# ESP32_With_USBC.net
KiCad netlist of a schematic drawn in Altium Designer
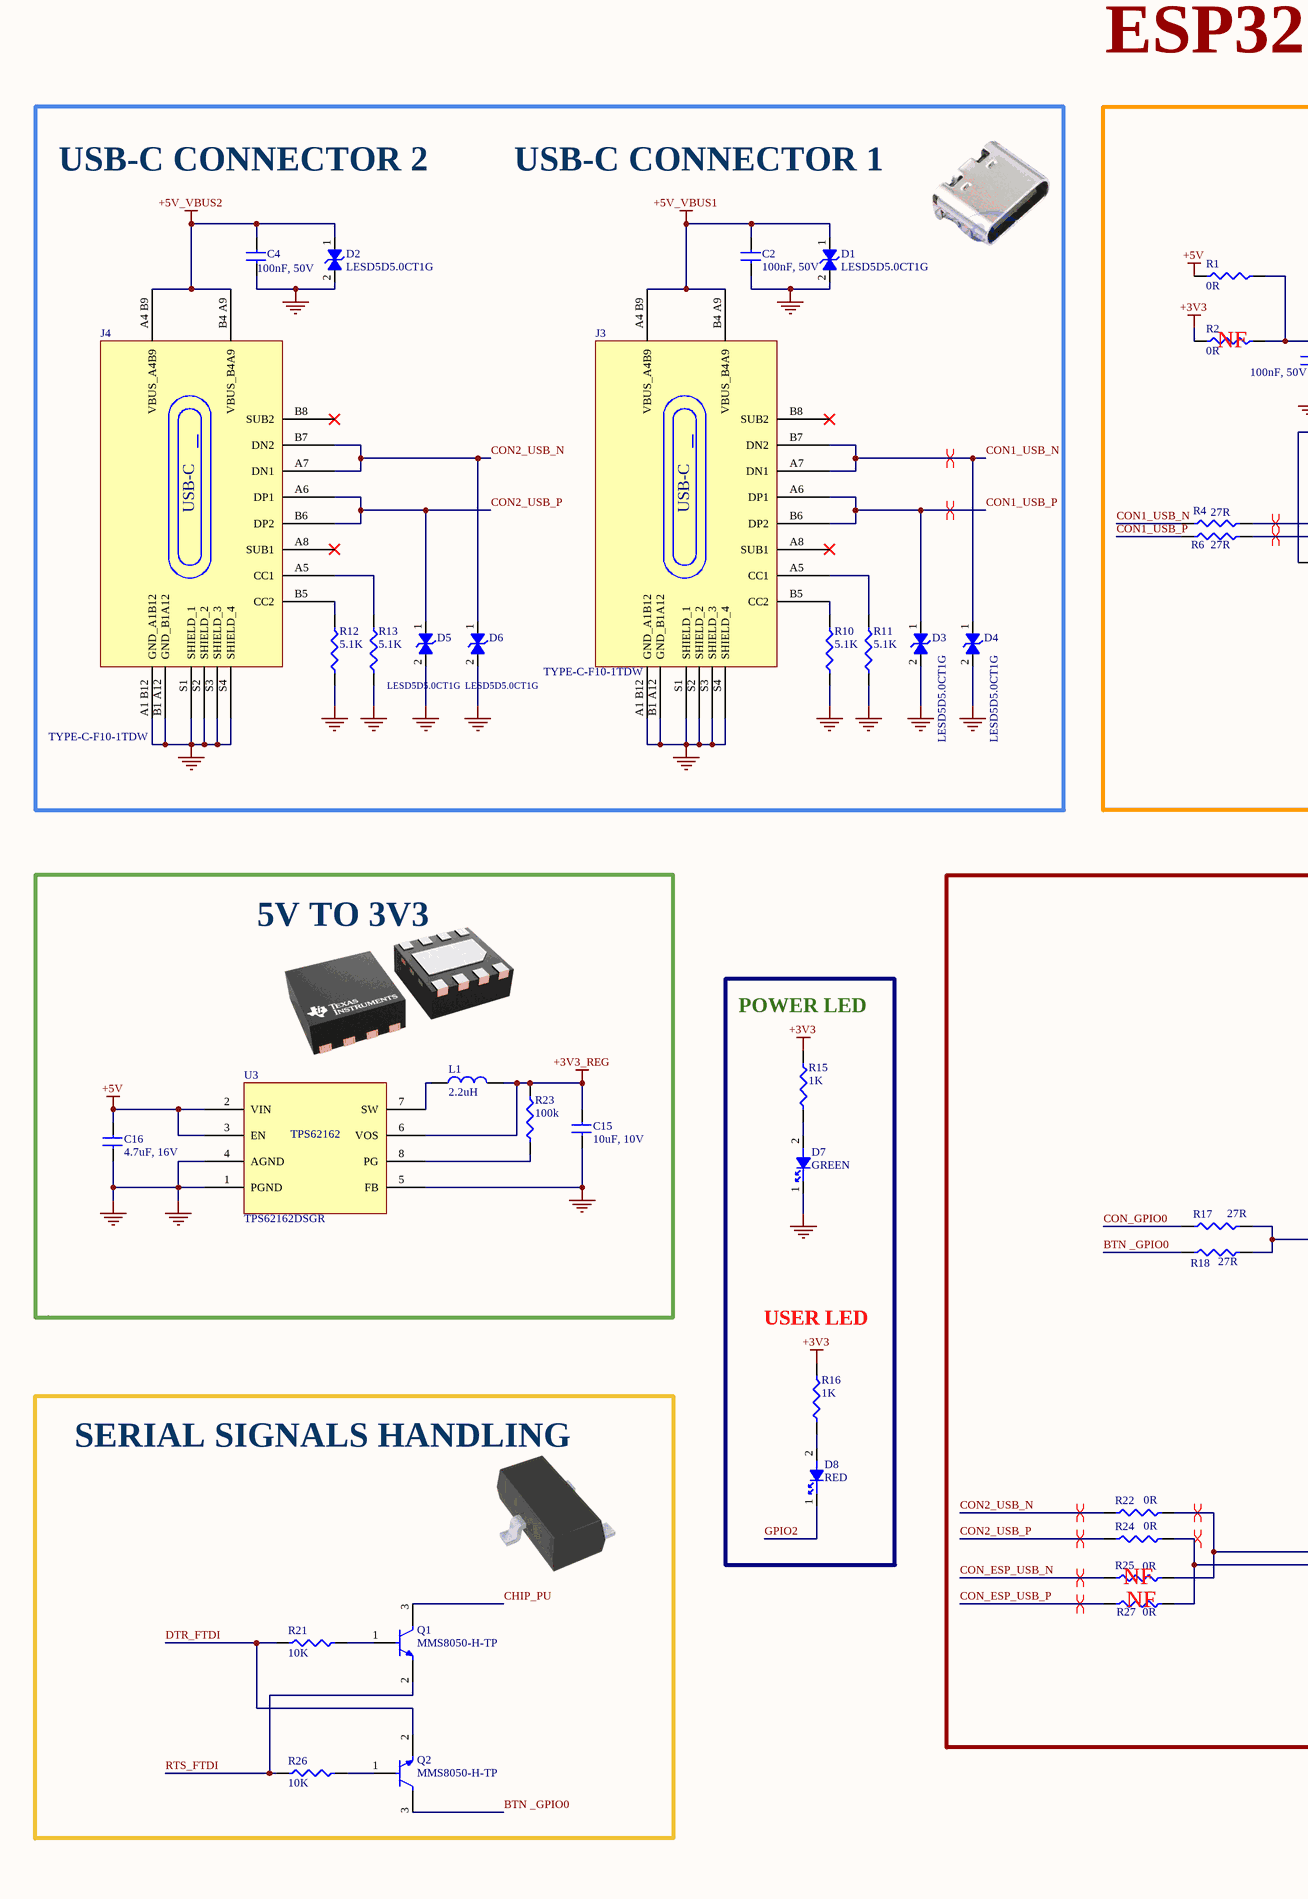
[diagram p0: ESP32 With USBC.SchDoc, left]
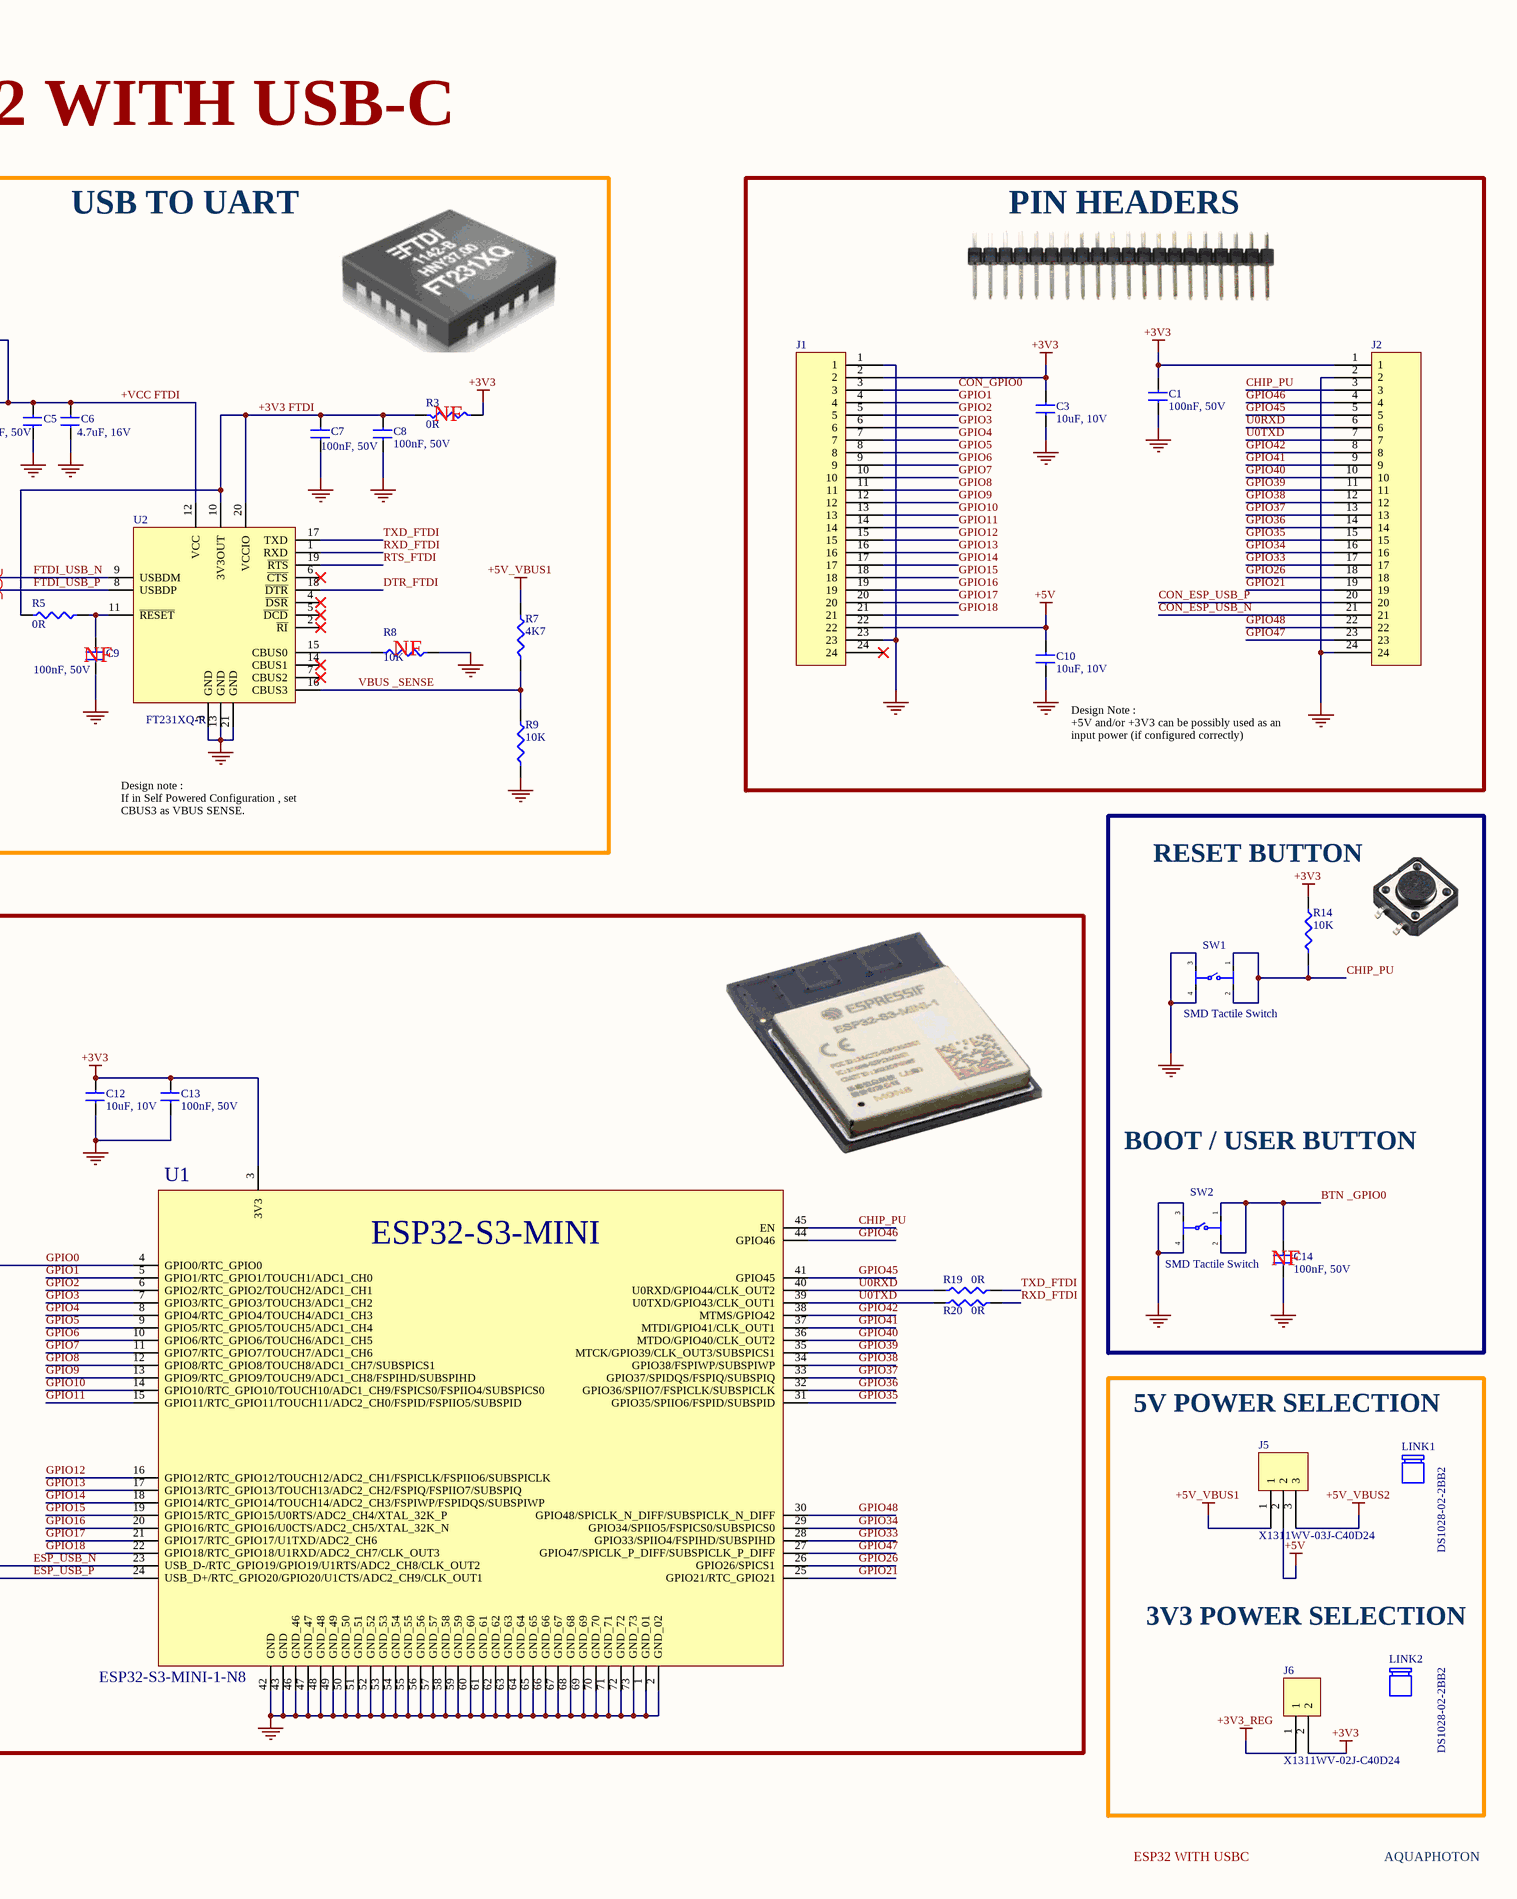
[diagram p1: ESP32 With USBC.SchDoc, right]

(export (version "E")
  (design (tool "Eeschema 10.0.6"))
  (components
    (comp (ref "C1")
      (value "100nF, 50V")
      (footprint "CAP_SMD_0402_Samsung")
      (description "CAP CER 0.1UF 50V X7R 0402")
      (fields
        (field (name "MANUFACTURER") "Samsung")
        (field (name "MANUFACTURER PART NUMBER") "CL05B104KB54PNC")
      )
      (libsource (lib "Schlib") (part "CL05B104KB54PNC"))
    )
    (comp (ref "C2")
      (value "100nF, 50V")
      (footprint "CAP_SMD_0402_Samsung")
      (description "CAP CER 0.1UF 50V X7R 0402")
      (fields
        (field (name "MANUFACTURER") "Samsung")
        (field (name "MANUFACTURER PART NUMBER") "CL05B104KB54PNC")
      )
      (libsource (lib "Schlib") (part "CL05B104KB54PNC"))
    )
    (comp (ref "C3")
      (value "10uF, 10V")
      (footprint "CAP_SMD_0402_Samsung")
      (description "CAP CER 10UF 10V X5R 0402")
      (fields
        (field (name "MANUFACTURER") "Samsung")
        (field (name "MANUFACTURER PART NUMBER") "CL05A106MP8NUB8")
      )
      (libsource (lib "Schlib") (part "CL05A106MP8NUB8"))
    )
    (comp (ref "C4")
      (value "100nF, 50V")
      (footprint "CAP_SMD_0402_Samsung")
      (description "CAP CER 0.1UF 50V X7R 0402")
      (fields
        (field (name "MANUFACTURER") "Samsung")
        (field (name "MANUFACTURER PART NUMBER") "CL05B104KB54PNC")
      )
      (libsource (lib "Schlib") (part "CL05B104KB54PNC"))
    )
    (comp (ref "C5")
      (value "100nF, 50V")
      (footprint "CAP_SMD_0402_Samsung")
      (description "CAP CER 0.1UF 50V X7R 0402")
      (fields
        (field (name "MANUFACTURER") "Samsung")
        (field (name "MANUFACTURER PART NUMBER") "CL05B104KB54PNC")
      )
      (libsource (lib "Schlib") (part "CL05B104KB54PNC"))
    )
    (comp (ref "C6")
      (value "4.7uF, 16V")
      (footprint "CAP_SMD_0402_Samsung")
      (description "4.7 µF ±20% 16V Ceramic Capacitor X5R 0402 (1005 Metric)")
      (fields
        (field (name "MANUFACTURER") "Samsung")
        (field (name "MANUFACTURER PART NUMBER") "CL05A475MO5NUNC")
      )
      (libsource (lib "Schlib") (part "CL05A475MO5NUNC"))
    )
    (comp (ref "C7")
      (value "100nF, 50V")
      (footprint "CAP_SMD_0402_Samsung")
      (description "CAP CER 0.1UF 50V X7R 0402")
      (fields
        (field (name "MANUFACTURER") "Samsung")
        (field (name "MANUFACTURER PART NUMBER") "CL05B104KB54PNC")
      )
      (libsource (lib "Schlib") (part "CL05B104KB54PNC"))
    )
    (comp (ref "C8")
      (value "100nF, 50V")
      (footprint "CAP_SMD_0402_Samsung")
      (description "CAP CER 0.1UF 50V X7R 0402")
      (fields
        (field (name "MANUFACTURER") "Samsung")
        (field (name "MANUFACTURER PART NUMBER") "CL05B104KB54PNC")
      )
      (libsource (lib "Schlib") (part "CL05B104KB54PNC"))
    )
    (comp (ref "C9")
      (value "100nF, 50V")
      (footprint "CAP_SMD_0402_Samsung")
      (description "CAP CER 0.1UF 50V X7R 0402")
      (fields
        (field (name "MANUFACTURER") "Samsung")
        (field (name "MANUFACTURER PART NUMBER") "CL05B104KB54PNC")
      )
      (libsource (lib "Schlib") (part "CL05B104KB54PNC"))
    )
    (comp (ref "C10")
      (value "10uF, 10V")
      (footprint "CAP_SMD_0402_Samsung")
      (description "CAP CER 10UF 10V X5R 0402")
      (fields
        (field (name "MANUFACTURER") "Samsung")
        (field (name "MANUFACTURER PART NUMBER") "CL05A106MP8NUB8")
      )
      (libsource (lib "Schlib") (part "CL05A106MP8NUB8"))
    )
    (comp (ref "C12")
      (value "10uF, 10V")
      (footprint "CAP_SMD_0402_Samsung")
      (description "CAP CER 10UF 10V X5R 0402")
      (fields
        (field (name "MANUFACTURER") "Samsung")
        (field (name "MANUFACTURER PART NUMBER") "CL05A106MP8NUB8")
      )
      (libsource (lib "Schlib") (part "CL05A106MP8NUB8"))
    )
    (comp (ref "C13")
      (value "100nF, 50V")
      (footprint "CAP_SMD_0402_Samsung")
      (description "CAP CER 0.1UF 50V X7R 0402")
      (fields
        (field (name "MANUFACTURER") "Samsung")
        (field (name "MANUFACTURER PART NUMBER") "CL05B104KB54PNC")
      )
      (libsource (lib "Schlib") (part "CL05B104KB54PNC"))
    )
    (comp (ref "C14")
      (value "100nF, 50V")
      (footprint "CAP_SMD_0402_Samsung")
      (description "CAP CER 0.1UF 50V X7R 0402")
      (fields
        (field (name "MANUFACTURER") "Samsung")
        (field (name "MANUFACTURER PART NUMBER") "CL05B104KB54PNC")
      )
      (libsource (lib "Schlib") (part "CL05B104KB54PNC"))
    )
    (comp (ref "C15")
      (value "10uF, 10V")
      (footprint "CAP_SMD_0402_Samsung")
      (description "CAP CER 10UF 10V X5R 0402")
      (fields
        (field (name "MANUFACTURER") "Samsung")
        (field (name "MANUFACTURER PART NUMBER") "CL05A106MP8NUB8")
      )
      (libsource (lib "Schlib") (part "CL05A106MP8NUB8"))
    )
    (comp (ref "C16")
      (value "4.7uF, 16V")
      (footprint "CAP_SMD_0402_Samsung")
      (description "4.7 µF ±20% 16V Ceramic Capacitor X5R 0402 (1005 Metric)")
      (fields
        (field (name "MANUFACTURER") "Samsung")
        (field (name "MANUFACTURER PART NUMBER") "CL05A475MO5NUNC")
      )
      (libsource (lib "Schlib") (part "CL05A475MO5NUNC"))
    )
    (comp (ref "D1")
      (value "LESD5D5.0CT1G")
      (footprint "TVS-Diode")
      (description "9.4A 18.6V 5.6V Bidirectional 5V SOD-523 ESD and Surge Protection (TVS/ESD) ROHS")
      (fields (field (name "MANUFACTURER") "LRC"))
      (libsource (lib "Schlib") (part "LESD5D5.0CT1G"))
    )
    (comp (ref "D2")
      (value "LESD5D5.0CT1G")
      (footprint "TVS-Diode")
      (description "9.4A 18.6V 5.6V Bidirectional 5V SOD-523 ESD and Surge Protection (TVS/ESD) ROHS")
      (fields (field (name "MANUFACTURER") "LRC"))
      (libsource (lib "Schlib") (part "LESD5D5.0CT1G"))
    )
    (comp (ref "D3")
      (value "LESD5D5.0CT1G")
      (footprint "TVS-Diode")
      (description "9.4A 18.6V 5.6V Bidirectional 5V SOD-523 ESD and Surge Protection (TVS/ESD) ROHS")
      (fields (field (name "MANUFACTURER") "LRC"))
      (libsource (lib "Schlib") (part "LESD5D5.0CT1G"))
    )
    (comp (ref "D4")
      (value "LESD5D5.0CT1G")
      (footprint "TVS-Diode")
      (description "9.4A 18.6V 5.6V Bidirectional 5V SOD-523 ESD and Surge Protection (TVS/ESD) ROHS")
      (fields (field (name "MANUFACTURER") "LRC"))
      (libsource (lib "Schlib") (part "LESD5D5.0CT1G"))
    )
    (comp (ref "D5")
      (value "LESD5D5.0CT1G")
      (footprint "TVS-Diode")
      (description "9.4A 18.6V 5.6V Bidirectional 5V SOD-523 ESD and Surge Protection (TVS/ESD) ROHS")
      (fields (field (name "MANUFACTURER") "LRC"))
      (libsource (lib "Schlib") (part "LESD5D5.0CT1G"))
    )
    (comp (ref "D6")
      (value "LESD5D5.0CT1G")
      (footprint "TVS-Diode")
      (description "9.4A 18.6V 5.6V Bidirectional 5V SOD-523 ESD and Surge Protection (TVS/ESD) ROHS")
      (fields (field (name "MANUFACTURER") "LRC"))
      (libsource (lib "Schlib") (part "LESD5D5.0CT1G"))
    )
    (comp (ref "D7")
      (value "GREEN")
      (footprint "LED_0402_G")
      (description "LED GREEN 0402 SMD")
      (fields
        (field (name "MANUFACTURER") "Vishay")
        (field (name "MANUFACTURER PART NUMBER") "VLMG1500-GS08")
      )
      (libsource (lib "Schlib") (part "VLMG1500-GS08"))
    )
    (comp (ref "D8")
      (value "RED")
      (footprint "LED_0402_R")
      (description "LED RED 0402 SMD")
      (fields
        (field (name "MANUFACTURER") "Vishay")
        (field (name "MANUFACTURER PART NUMBER") "VLMS1500-GS08")
      )
      (libsource (lib "Schlib") (part "VLMS1500-GS08"))
    )
    (comp (ref "J1")
      (value "X5511WV-24-C35D35-1000")
      (footprint "HDR_1X24_2.54MM")
      (fields (field (name "MANUFACTURER") "XKB Connection"))
      (libsource (lib "Schlib") (part "X6511WV-24H-C60D30"))
    )
    (comp (ref "J2")
      (value "X5511WV-24-C35D35-1000")
      (footprint "HDR_1X24_2.54MM")
      (fields (field (name "MANUFACTURER") "XKB Connection"))
      (libsource (lib "") (part "X6511WV-24H-C60D30_1"))
    )
    (comp (ref "J3")
      (value "TYPE-C-F10-1TDW")
      (footprint "USB-C")
      (description "16P Type-C SMD USB Connectors")
      (fields (field (name "MANUFACTURER") "XYECONN"))
      (libsource (lib "Schlib") (part "TYPE-C-F10-1TDW"))
    )
    (comp (ref "J4")
      (value "TYPE-C-F10-1TDW")
      (footprint "USB-C")
      (description "16P Type-C SMD USB Connectors")
      (fields (field (name "MANUFACTURER") "XYECONN"))
      (libsource (lib "Schlib") (part "TYPE-C-F10-1TDW"))
    )
    (comp (ref "J5")
      (value "X1311WV-03J-C40D24")
      (footprint "HDR_1X3_1.27mm - duplicate")
      (fields (field (name "MANUFACTURER") "XKB Connection"))
      (libsource (lib "Schlib") (part "X1311WV-03J-C40D24"))
    )
    (comp (ref "J6")
      (value "X1311WV-02J-C40D24")
      (footprint "HDR_1X2_1.27mm")
      (fields (field (name "MANUFACTURER") "XKB Connection"))
      (libsource (lib "Schlib") (part "X1311WV-02J-C40D24"))
    )
    (comp (ref "L1")
      (value "2.2uH")
      (footprint "Inductor_SMD_2.2uH")
      (description "2.2 µH Shielded Multilayer Inductor 1 A 195mOhm Max 0805 (2012 Metric)")
      (fields
        (field (name "MANUFACTURER") "TDK")
        (field (name "MANUFACTURER PART NUMBER") "MLP2012H2R2MT0S1")
      )
      (libsource (lib "Schlib") (part "MLP2012H2R2MT0S1"))
    )
    (comp (ref "LINK1")
      (value "DS1028-02-2BB2")
      (description "CONN SHUNT  1.27mm")
      (fields (field (name "MANUFACTURER") "CONNFLY Elec"))
      (libsource (lib "Schlib") (part "DS1028-02-2BB2"))
    )
    (comp (ref "LINK2")
      (value "DS1028-02-2BB2")
      (description "CONN SHUNT  1.27mm")
      (fields (field (name "MANUFACTURER") "CONNFLY Elec"))
      (libsource (lib "Schlib") (part "DS1028-02-2BB2"))
    )
    (comp (ref "Q1")
      (value "MMS8050-H-TP")
      (footprint "SOT_Transistor")
      (description "Bipolar (BJT) Transistor NPN 25 V 500 mA 150MHz 300 mW Surface Mount SOT-23")
      (fields (field (name "MANUFACTURER") "MCC"))
      (libsource (lib "Schlib") (part "MMS8050-H-TP"))
    )
    (comp (ref "Q2")
      (value "MMS8050-H-TP")
      (footprint "SOT_Transistor")
      (description "Bipolar (BJT) Transistor NPN 25 V 500 mA 150MHz 300 mW Surface Mount SOT-23")
      (fields (field (name "MANUFACTURER") "MCC"))
      (libsource (lib "Schlib") (part "MMS8050-H-TP"))
    )
    (comp (ref "R1")
      (value "0R")
      (footprint "RES_SMD_0402")
      (description "0 Ohms Jumper Chip Resistor 0402 (1005 Metric) Moisture Resistant Thick Film")
      (fields
        (field (name "MANUFACTURER") "Yageo")
        (field (name "MANUFACTURER PART NUMBER") "RC0402JR-070RL")
      )
      (libsource (lib "Schlib") (part "RC0402JR-070RL"))
    )
    (comp (ref "R2")
      (value "0R")
      (footprint "RES_SMD_0402")
      (description "0 Ohms Jumper Chip Resistor 0402 (1005 Metric) Moisture Resistant Thick Film")
      (fields
        (field (name "MANUFACTURER") "Yageo")
        (field (name "MANUFACTURER PART NUMBER") "RC0402JR-070RL")
      )
      (libsource (lib "Schlib") (part "RC0402JR-070RL"))
    )
    (comp (ref "R3")
      (value "0R")
      (footprint "RES_SMD_0402")
      (description "0 Ohms Jumper Chip Resistor 0402 (1005 Metric) Moisture Resistant Thick Film")
      (fields
        (field (name "MANUFACTURER") "Yageo")
        (field (name "MANUFACTURER PART NUMBER") "RC0402JR-070RL")
      )
      (libsource (lib "Schlib") (part "RC0402JR-070RL"))
    )
    (comp (ref "R4")
      (value "27R")
      (footprint "RES_SMD_0402")
      (description "27 Ohms ±1% 0.063W, 1/16W Chip Resistor 0402 (1005 Metric) Moisture Resistant Thick Film")
      (fields
        (field (name "MANUFACTURER") "Yageo")
        (field (name "MANUFACTURER PART NUMBER") "RC0402FR-0727RL")
      )
      (libsource (lib "Schlib") (part "RC0402FR-0727RL"))
    )
    (comp (ref "R5")
      (value "0R")
      (footprint "RES_SMD_0402")
      (description "0 Ohms Jumper Chip Resistor 0402 (1005 Metric) Moisture Resistant Thick Film")
      (fields
        (field (name "MANUFACTURER") "Yageo")
        (field (name "MANUFACTURER PART NUMBER") "RC0402JR-070RL")
      )
      (libsource (lib "Schlib") (part "RC0402JR-070RL"))
    )
    (comp (ref "R6")
      (value "27R")
      (footprint "RES_SMD_0402")
      (description "27 Ohms ±1% 0.063W, 1/16W Chip Resistor 0402 (1005 Metric) Moisture Resistant Thick Film")
      (fields
        (field (name "MANUFACTURER") "Yageo")
        (field (name "MANUFACTURER PART NUMBER") "RC0402FR-0727RL")
      )
      (libsource (lib "Schlib") (part "RC0402FR-0727RL"))
    )
    (comp (ref "R7")
      (value "4K7")
      (footprint "RES_SMD_0402")
      (description "4.7 kOhms ±1% 0.063W, 1/16W Chip Resistor 0402 (1005 Metric) Moisture Resistant Thick Film")
      (fields
        (field (name "MANUFACTURER") "Yageo")
        (field (name "MANUFACTURER PART NUMBER") "RC0402FR-074K7L")
      )
      (libsource (lib "Schlib") (part "RC0402FR-074K7L"))
    )
    (comp (ref "R8")
      (value "10K")
      (footprint "RES_SMD_0402")
      (description "62.5mW Thick Film Resistors 50V ±100ppm/℃ ±1% 10kΩ 0402 Chip Resistor - Surface Mount ROHS")
      (fields
        (field (name "MANUFACTURER") "Yageo")
        (field (name "MANUFACTURER PART NUMBER") "AC0402FR-0710KL")
      )
      (libsource (lib "Schlib") (part "AC0402FR-0710KL"))
    )
    (comp (ref "R9")
      (value "10K")
      (footprint "RES_SMD_0402")
      (description "62.5mW Thick Film Resistors 50V ±100ppm/℃ ±1% 10kΩ 0402 Chip Resistor - Surface Mount ROHS")
      (fields
        (field (name "MANUFACTURER") "Yageo")
        (field (name "MANUFACTURER PART NUMBER") "AC0402FR-0710KL")
      )
      (libsource (lib "Schlib") (part "AC0402FR-0710KL"))
    )
    (comp (ref "R10")
      (value "5.1K")
      (footprint "RES_SMD_0402")
      (fields
        (field (name "MANUFACTURER") "Yageo")
        (field (name "MANUFACTURER PART NUMBER") "AC0402FR-075K1L")
      )
      (libsource (lib "Schlib") (part "AC0402FR-075K1L"))
    )
    (comp (ref "R11")
      (value "5.1K")
      (footprint "RES_SMD_0402")
      (fields
        (field (name "MANUFACTURER") "Yageo")
        (field (name "MANUFACTURER PART NUMBER") "AC0402FR-075K1L")
      )
      (libsource (lib "Schlib") (part "AC0402FR-075K1L"))
    )
    (comp (ref "R12")
      (value "5.1K")
      (footprint "RES_SMD_0402")
      (fields
        (field (name "MANUFACTURER") "Yageo")
        (field (name "MANUFACTURER PART NUMBER") "AC0402FR-075K1L")
      )
      (libsource (lib "Schlib") (part "AC0402FR-075K1L"))
    )
    (comp (ref "R13")
      (value "5.1K")
      (footprint "RES_SMD_0402")
      (fields
        (field (name "MANUFACTURER") "Yageo")
        (field (name "MANUFACTURER PART NUMBER") "AC0402FR-075K1L")
      )
      (libsource (lib "Schlib") (part "AC0402FR-075K1L"))
    )
    (comp (ref "R14")
      (value "10K")
      (footprint "RES_SMD_0402")
      (description "62.5mW Thick Film Resistors 50V ±100ppm/℃ ±1% 10kΩ 0402 Chip Resistor - Surface Mount ROHS")
      (fields
        (field (name "MANUFACTURER") "Yageo")
        (field (name "MANUFACTURER PART NUMBER") "AC0402FR-0710KL")
      )
      (libsource (lib "Schlib") (part "AC0402FR-0710KL"))
    )
    (comp (ref "R15")
      (value "1K")
      (footprint "RES_SMD_0402")
      (description "RES 1K OHM 1% 1/16W 0402")
      (fields
        (field (name "MANUFACTURER") "Yageo")
        (field (name "MANUFACTURER PART NUMBER") "RC0402FR-071KL")
      )
      (libsource (lib "Schlib") (part "RC0402FR-071KL"))
    )
    (comp (ref "R16")
      (value "1K")
      (footprint "RES_SMD_0402")
      (description "RES 1K OHM 1% 1/16W 0402")
      (fields
        (field (name "MANUFACTURER") "Yageo")
        (field (name "MANUFACTURER PART NUMBER") "RC0402FR-071KL")
      )
      (libsource (lib "Schlib") (part "RC0402FR-071KL"))
    )
    (comp (ref "R17")
      (value "27R")
      (footprint "RES_SMD_0402")
      (description "27 Ohms ±1% 0.063W, 1/16W Chip Resistor 0402 (1005 Metric) Moisture Resistant Thick Film")
      (fields
        (field (name "MANUFACTURER") "Yageo")
        (field (name "MANUFACTURER PART NUMBER") "RC0402FR-0727RL")
      )
      (libsource (lib "Schlib") (part "RC0402FR-0727RL"))
    )
    (comp (ref "R18")
      (value "27R")
      (footprint "RES_SMD_0402")
      (description "27 Ohms ±1% 0.063W, 1/16W Chip Resistor 0402 (1005 Metric) Moisture Resistant Thick Film")
      (fields
        (field (name "MANUFACTURER") "Yageo")
        (field (name "MANUFACTURER PART NUMBER") "RC0402FR-0727RL")
      )
      (libsource (lib "Schlib") (part "RC0402FR-0727RL"))
    )
    (comp (ref "R19")
      (value "0R")
      (footprint "RES_SMD_0402")
      (description "0 Ohms Jumper Chip Resistor 0402 (1005 Metric) Moisture Resistant Thick Film")
      (fields
        (field (name "MANUFACTURER") "Yageo")
        (field (name "MANUFACTURER PART NUMBER") "RC0402JR-070RL")
      )
      (libsource (lib "Schlib") (part "RC0402JR-070RL"))
    )
    (comp (ref "R20")
      (value "0R")
      (footprint "RES_SMD_0402")
      (description "0 Ohms Jumper Chip Resistor 0402 (1005 Metric) Moisture Resistant Thick Film")
      (fields
        (field (name "MANUFACTURER") "Yageo")
        (field (name "MANUFACTURER PART NUMBER") "RC0402JR-070RL")
      )
      (libsource (lib "Schlib") (part "RC0402JR-070RL"))
    )
    (comp (ref "R21")
      (value "10K")
      (footprint "RES_SMD_0402")
      (description "62.5mW Thick Film Resistors 50V ±100ppm/℃ ±1% 10kΩ 0402 Chip Resistor - Surface Mount ROHS")
      (fields
        (field (name "MANUFACTURER") "Yageo")
        (field (name "MANUFACTURER PART NUMBER") "AC0402FR-0710KL")
      )
      (libsource (lib "Schlib") (part "AC0402FR-0710KL"))
    )
    (comp (ref "R22")
      (value "0R")
      (footprint "RES_SMD_0402")
      (description "0 Ohms Jumper Chip Resistor 0402 (1005 Metric) Moisture Resistant Thick Film")
      (fields
        (field (name "MANUFACTURER") "Yageo")
        (field (name "MANUFACTURER PART NUMBER") "RC0402JR-070RL")
      )
      (libsource (lib "Schlib") (part "RC0402JR-070RL"))
    )
    (comp (ref "R23")
      (value "100k")
      (footprint "RES_SMD_0402")
      (description "RES SMD 100K OHM 1% 1/16W 0402")
      (fields
        (field (name "MANUFACTURER") "Yageo")
        (field (name "MANUFACTURER PART NUMBER") "AC0402FR-07100KL")
      )
      (libsource (lib "Schlib") (part "AC0402FR-07100KL"))
    )
    (comp (ref "R24")
      (value "0R")
      (footprint "RES_SMD_0402")
      (description "0 Ohms Jumper Chip Resistor 0402 (1005 Metric) Moisture Resistant Thick Film")
      (fields
        (field (name "MANUFACTURER") "Yageo")
        (field (name "MANUFACTURER PART NUMBER") "RC0402JR-070RL")
      )
      (libsource (lib "Schlib") (part "RC0402JR-070RL"))
    )
    (comp (ref "R25")
      (value "0R")
      (footprint "RES_SMD_0402")
      (description "0 Ohms Jumper Chip Resistor 0402 (1005 Metric) Moisture Resistant Thick Film")
      (fields
        (field (name "MANUFACTURER") "Yageo")
        (field (name "MANUFACTURER PART NUMBER") "RC0402JR-070RL")
      )
      (libsource (lib "Schlib") (part "RC0402JR-070RL"))
    )
    (comp (ref "R26")
      (value "10K")
      (footprint "RES_SMD_0402")
      (description "62.5mW Thick Film Resistors 50V ±100ppm/℃ ±1% 10kΩ 0402 Chip Resistor - Surface Mount ROHS")
      (fields
        (field (name "MANUFACTURER") "Yageo")
        (field (name "MANUFACTURER PART NUMBER") "AC0402FR-0710KL")
      )
      (libsource (lib "Schlib") (part "AC0402FR-0710KL"))
    )
    (comp (ref "R27")
      (value "0R")
      (footprint "RES_SMD_0402")
      (description "0 Ohms Jumper Chip Resistor 0402 (1005 Metric) Moisture Resistant Thick Film")
      (fields
        (field (name "MANUFACTURER") "Yageo")
        (field (name "MANUFACTURER PART NUMBER") "RC0402JR-070RL")
      )
      (libsource (lib "Schlib") (part "RC0402JR-070RL"))
    )
    (comp (ref "SW1")
      (value "SMD Tactile Switch")
      (footprint "Tactile Switch_SMD")
      (description "SMD Tactile Switches ROHS")
      (fields
        (field (name "MANUFACTURER") "G-Switch")
        (field (name "MANUFACTURER PART NUMBER") "GT-TC089A-H043-L1")
      )
      (libsource (lib "Schlib") (part "GT-TC089A-H043-L1"))
    )
    (comp (ref "SW2")
      (value "SMD Tactile Switch")
      (footprint "Tactile Switch_SMD")
      (description "SMD Tactile Switches ROHS")
      (fields
        (field (name "MANUFACTURER") "G-Switch")
        (field (name "MANUFACTURER PART NUMBER") "GT-TC089A-H043-L1")
      )
      (libsource (lib "Schlib") (part "GT-TC089A-H043-L1"))
    )
    (comp (ref "U1")
      (value "ESP32-S3-MINI-1-N8")
      (footprint "ESP32-S3-MINI-1-N8")
      (description "SMD module, ESP32-S3FN8, 8 MB SPI flash, PCB antenna")
      (fields (field (name "MANUFACTURER") "Espressif Systems"))
      (libsource (lib "Schlib") (part "ESP32-S3-MINI-1-N8"))
    )
    (comp (ref "U2")
      (value "FT231XQ-R")
      (footprint "USB TO UART _FTDI")
      (description "IC USB SERIAL FULL UART 20QFN")
      (fields (field (name "MANUFACTURER") "FTDI"))
      (libsource (lib "Schlib") (part "FT231XQ-R"))
    )
    (comp (ref "U3")
      (value "TPS62162DSGR")
      (footprint "BUCK_TPS62162DSGR")
      (description "Buck Switching Regulator IC Positive Fixed 3.3V 1 Output 1A 8-WFDFN Exposed Pad")
      (fields (field (name "MANUFACTURER") "Texas Instruments"))
      (libsource (lib "Schlib") (part "TPS62162DSGR"))
    )
  )
  (nets
    (net (code "1") (name "+3V3") (class "Default")
      (node (ref "C1") (pin "2") (pinfunction "2_2") (pintype "passive"))
      (node (ref "C12") (pin "2") (pinfunction "2_2") (pintype "passive"))
      (node (ref "C13") (pin "2") (pinfunction "2_2") (pintype "passive"))
      (node (ref "C3") (pin "2") (pinfunction "2_2") (pintype "passive"))
      (node (ref "J1") (pin "2") (pinfunction "2_2") (pintype "passive"))
      (node (ref "J2") (pin "1") (pinfunction "1_1") (pintype "passive"))
      (node (ref "J6") (pin "2") (pinfunction "2_2") (pintype "passive"))
      (node (ref "R14") (pin "2") (pinfunction "2_2") (pintype "passive"))
      (node (ref "R15") (pin "2") (pinfunction "2_2") (pintype "passive"))
      (node (ref "R16") (pin "2") (pinfunction "2_2") (pintype "passive"))
      (node (ref "R2") (pin "1") (pinfunction "1_1") (pintype "passive"))
      (node (ref "R3") (pin "1") (pinfunction "1_1") (pintype "passive"))
      (node (ref "U1") (pin "3") (pinfunction "3V3_3") (pintype "passive"))
    )
    (net (code "2") (name "+3V3_REG") (class "Default")
      (node (ref "C15") (pin "2") (pinfunction "2_2") (pintype "passive"))
      (node (ref "J6") (pin "1") (pinfunction "1_1") (pintype "passive"))
      (node (ref "L1") (pin "2") (pinfunction "2_2") (pintype "passive"))
      (node (ref "R23") (pin "2") (pinfunction "2_2") (pintype "passive"))
      (node (ref "U3") (pin "6") (pinfunction "VOS_6") (pintype "passive"))
    )
    (net (code "3") (name "+5V") (class "Default")
      (node (ref "C10") (pin "2") (pinfunction "2_2") (pintype "passive"))
      (node (ref "C16") (pin "2") (pinfunction "2_2") (pintype "passive"))
      (node (ref "J1") (pin "22") (pinfunction "22_22") (pintype "passive"))
      (node (ref "J5") (pin "2") (pinfunction "2_2") (pintype "passive"))
      (node (ref "R1") (pin "1") (pinfunction "1_1") (pintype "passive"))
      (node (ref "U3") (pin "2") (pinfunction "VIN_2") (pintype "passive"))
      (node (ref "U3") (pin "3") (pinfunction "EN_3") (pintype "passive"))
    )
    (net (code "4") (name "+5V_VBUS1") (class "Default")
      (node (ref "C2") (pin "2") (pinfunction "2_2") (pintype "passive"))
      (node (ref "D1") (pin "1") (pinfunction "1_1") (pintype "passive"))
      (node (ref "J3") (pin "A4_B9") (pinfunction "VBUS_A4B9_A4_B9") (pintype "passive"))
      (node (ref "J3") (pin "B4_A9") (pinfunction "VBUS_B4A9_B4_A9") (pintype "passive"))
      (node (ref "J5") (pin "1") (pinfunction "1_1") (pintype "passive"))
      (node (ref "R7") (pin "2") (pinfunction "2_2") (pintype "passive"))
    )
    (net (code "5") (name "+5V_VBUS2") (class "Default")
      (node (ref "C4") (pin "2") (pinfunction "2_2") (pintype "passive"))
      (node (ref "D2") (pin "1") (pinfunction "1_1") (pintype "passive"))
      (node (ref "J4") (pin "A4_B9") (pinfunction "VBUS_A4B9_A4_B9") (pintype "passive"))
      (node (ref "J4") (pin "B4_A9") (pinfunction "VBUS_B4A9_B4_A9") (pintype "passive"))
      (node (ref "J5") (pin "3") (pinfunction "3_3") (pintype "passive"))
    )
    (net (code "6") (name "/+3V3 FTDI") (class "Default")
      (node (ref "C7") (pin "2") (pinfunction "2_2") (pintype "passive"))
      (node (ref "C8") (pin "2") (pinfunction "2_2") (pintype "passive"))
      (node (ref "R3") (pin "2") (pinfunction "2_2") (pintype "passive"))
      (node (ref "R5") (pin "1") (pinfunction "1_1") (pintype "passive"))
      (node (ref "U2") (pin "10") (pinfunction "3V3OUT_10") (pintype "passive"))
      (node (ref "U2") (pin "20") (pinfunction "VCCIO_20") (pintype "passive"))
    )
    (net (code "7") (name "/+VCC FTDI") (class "Default")
      (node (ref "C5") (pin "2") (pinfunction "2_2") (pintype "passive"))
      (node (ref "C6") (pin "2") (pinfunction "2_2") (pintype "passive"))
      (node (ref "R1") (pin "2") (pinfunction "2_2") (pintype "passive"))
      (node (ref "R2") (pin "2") (pinfunction "2_2") (pintype "passive"))
      (node (ref "U2") (pin "12") (pinfunction "VCC_12") (pintype "passive"))
    )
    (net (code "8") (name "/BTN _GPIO0") (class "Default")
      (node (ref "C14") (pin "2") (pinfunction "2_2") (pintype "passive"))
      (node (ref "Q2") (pin "3") (pinfunction "C_3") (pintype "passive"))
      (node (ref "R18") (pin "1") (pinfunction "1_1") (pintype "passive"))
      (node (ref "SW2") (pin "1") (pinfunction "1_1") (pintype "passive"))
      (node (ref "SW2") (pin "2") (pinfunction "2_2") (pintype "passive"))
    )
    (net (code "9") (name "/CHIP_PU") (class "Default")
      (node (ref "J2") (pin "3") (pinfunction "3_3") (pintype "passive"))
      (node (ref "Q1") (pin "3") (pinfunction "C_3") (pintype "passive"))
      (node (ref "R14") (pin "1") (pinfunction "1_1") (pintype "passive"))
      (node (ref "SW1") (pin "1") (pinfunction "1_1") (pintype "passive"))
      (node (ref "SW1") (pin "2") (pinfunction "2_2") (pintype "passive"))
      (node (ref "U1") (pin "45") (pinfunction "EN_45") (pintype "passive"))
    )
    (net (code "10") (name "/CON1_USB_N") (class "Default")
      (node (ref "D4") (pin "1") (pinfunction "1_1") (pintype "passive"))
      (node (ref "J3") (pin "A7") (pinfunction "DN1_A7") (pintype "passive"))
      (node (ref "J3") (pin "B7") (pinfunction "DN2_B7") (pintype "passive"))
      (node (ref "R4") (pin "1") (pinfunction "1_1") (pintype "passive"))
    )
    (net (code "11") (name "/CON1_USB_P") (class "Default")
      (node (ref "D3") (pin "1") (pinfunction "1_1") (pintype "passive"))
      (node (ref "J3") (pin "A6") (pinfunction "DP1_A6") (pintype "passive"))
      (node (ref "J3") (pin "B6") (pinfunction "DP2_B6") (pintype "passive"))
      (node (ref "R6") (pin "1") (pinfunction "1_1") (pintype "passive"))
    )
    (net (code "12") (name "/CON2_USB_N") (class "Default")
      (node (ref "D6") (pin "1") (pinfunction "1_1") (pintype "passive"))
      (node (ref "J4") (pin "A7") (pinfunction "DN1_A7") (pintype "passive"))
      (node (ref "J4") (pin "B7") (pinfunction "DN2_B7") (pintype "passive"))
      (node (ref "R22") (pin "1") (pinfunction "1_1") (pintype "passive"))
    )
    (net (code "13") (name "/CON2_USB_P") (class "Default")
      (node (ref "D5") (pin "1") (pinfunction "1_1") (pintype "passive"))
      (node (ref "J4") (pin "A6") (pinfunction "DP1_A6") (pintype "passive"))
      (node (ref "J4") (pin "B6") (pinfunction "DP2_B6") (pintype "passive"))
      (node (ref "R24") (pin "1") (pinfunction "1_1") (pintype "passive"))
    )
    (net (code "14") (name "/CON_ESP_USB_N") (class "Default")
      (node (ref "J2") (pin "21") (pinfunction "21_21") (pintype "passive"))
      (node (ref "R25") (pin "1") (pinfunction "1_1") (pintype "passive"))
    )
    (net (code "15") (name "/CON_ESP_USB_P") (class "Default")
      (node (ref "J2") (pin "20") (pinfunction "20_20") (pintype "passive"))
      (node (ref "R27") (pin "1") (pinfunction "1_1") (pintype "passive"))
    )
    (net (code "16") (name "/CON_GPIO0") (class "Default")
      (node (ref "J1") (pin "3") (pinfunction "3_3") (pintype "passive"))
      (node (ref "R17") (pin "1") (pinfunction "1_1") (pintype "passive"))
    )
    (net (code "17") (name "/DTR_FTDI") (class "Default")
      (node (ref "Q2") (pin "2") (pinfunction "E_2") (pintype "passive"))
      (node (ref "R21") (pin "2") (pinfunction "2_2") (pintype "passive"))
      (node (ref "U2") (pin "18") (pinfunction "~{DTR}_18") (pintype "passive"))
    )
    (net (code "18") (name "/ESP_USB_N") (class "Default")
      (node (ref "R22") (pin "2") (pinfunction "2_2") (pintype "passive"))
      (node (ref "R25") (pin "2") (pinfunction "2_2") (pintype "passive"))
      (node (ref "U1") (pin "23") (pinfunction "USB_D-/RTC_GPIO19/GPIO19/U1RTS/ADC2_CH8/CLK_OUT2_23") (pintype "passive"))
    )
    (net (code "19") (name "/ESP_USB_P") (class "Default")
      (node (ref "R24") (pin "2") (pinfunction "2_2") (pintype "passive"))
      (node (ref "R27") (pin "2") (pinfunction "2_2") (pintype "passive"))
      (node (ref "U1") (pin "24") (pinfunction "USB_D+/RTC_GPIO20/GPIO20/U1CTS/ADC2_CH9/CLK_OUT1_24") (pintype "passive"))
    )
    (net (code "20") (name "/FTDI_USB_N") (class "Default")
      (node (ref "R4") (pin "2") (pinfunction "2_2") (pintype "passive"))
      (node (ref "U2") (pin "9") (pinfunction "USBDM_9") (pintype "passive"))
    )
    (net (code "21") (name "/FTDI_USB_P") (class "Default")
      (node (ref "R6") (pin "2") (pinfunction "2_2") (pintype "passive"))
      (node (ref "U2") (pin "8") (pinfunction "USBDP_8") (pintype "passive"))
    )
    (net (code "22") (name "/GPIO0") (class "Default")
      (node (ref "R17") (pin "2") (pinfunction "2_2") (pintype "passive"))
      (node (ref "R18") (pin "2") (pinfunction "2_2") (pintype "passive"))
      (node (ref "U1") (pin "4") (pinfunction "GPIO0/RTC_GPIO0_4") (pintype "passive"))
    )
    (net (code "23") (name "/GPIO1") (class "Default")
      (node (ref "J1") (pin "4") (pinfunction "4_4") (pintype "passive"))
      (node (ref "U1") (pin "5") (pinfunction "GPIO1/RTC_GPIO1/TOUCH1/ADC1_CH0_5") (pintype "passive"))
    )
    (net (code "24") (name "/GPIO2") (class "Default")
      (node (ref "D8") (pin "1") (pinfunction "1_1") (pintype "passive"))
      (node (ref "J1") (pin "5") (pinfunction "5_5") (pintype "passive"))
      (node (ref "U1") (pin "6") (pinfunction "GPIO2/RTC_GPIO2/TOUCH2/ADC1_CH1_6") (pintype "passive"))
    )
    (net (code "25") (name "/GPIO3") (class "Default")
      (node (ref "J1") (pin "6") (pinfunction "6_6") (pintype "passive"))
      (node (ref "U1") (pin "7") (pinfunction "GPIO3/RTC_GPIO3/TOUCH3/ADC1_CH2_7") (pintype "passive"))
    )
    (net (code "26") (name "/GPIO4") (class "Default")
      (node (ref "J1") (pin "7") (pinfunction "7_7") (pintype "passive"))
      (node (ref "U1") (pin "8") (pinfunction "GPIO4/RTC_GPIO4/TOUCH4/ADC1_CH3_8") (pintype "passive"))
    )
    (net (code "27") (name "/GPIO5") (class "Default")
      (node (ref "J1") (pin "8") (pinfunction "8_8") (pintype "passive"))
      (node (ref "U1") (pin "9") (pinfunction "GPIO5/RTC_GPIO5/TOUCH5/ADC1_CH4_9") (pintype "passive"))
    )
    (net (code "28") (name "/GPIO6") (class "Default")
      (node (ref "J1") (pin "9") (pinfunction "9_9") (pintype "passive"))
      (node (ref "U1") (pin "10") (pinfunction "GPIO6/RTC_GPIO6/TOUCH6/ADC1_CH5_10") (pintype "passive"))
    )
    (net (code "29") (name "/GPIO7") (class "Default")
      (node (ref "J1") (pin "10") (pinfunction "10_10") (pintype "passive"))
      (node (ref "U1") (pin "11") (pinfunction "GPIO7/RTC_GPIO7/TOUCH7/ADC1_CH6_11") (pintype "passive"))
    )
    (net (code "30") (name "/GPIO8") (class "Default")
      (node (ref "J1") (pin "11") (pinfunction "11_11") (pintype "passive"))
      (node (ref "U1") (pin "12") (pinfunction "GPIO8/RTC_GPIO8/TOUCH8/ADC1_CH7/SUBSPICS1_12") (pintype "passive"))
    )
    (net (code "31") (name "/GPIO9") (class "Default")
      (node (ref "J1") (pin "12") (pinfunction "12_12") (pintype "passive"))
      (node (ref "U1") (pin "13") (pinfunction "GPIO9/RTC_GPIO9/TOUCH9/ADC1_CH8/FSPIHD/SUBSPIHD_13") (pintype "passive"))
    )
    (net (code "32") (name "/GPIO10") (class "Default")
      (node (ref "J1") (pin "13") (pinfunction "13_13") (pintype "passive"))
      (node (ref "U1") (pin "14") (pinfunction "GPIO10/RTC_GPIO10/TOUCH10/ADC1_CH9/FSPICS0/FSPIIO4/SUBSPICS0_14") (pintype "passive"))
    )
    (net (code "33") (name "/GPIO11") (class "Default")
      (node (ref "J1") (pin "14") (pinfunction "14_14") (pintype "passive"))
      (node (ref "U1") (pin "15") (pinfunction "GPIO11/RTC_GPIO11/TOUCH11/ADC2_CH0/FSPID/FSPIIO5/SUBSPID_15") (pintype "passive"))
    )
    (net (code "34") (name "/GPIO12") (class "Default")
      (node (ref "J1") (pin "15") (pinfunction "15_15") (pintype "passive"))
      (node (ref "U1") (pin "16") (pinfunction "GPIO12/RTC_GPIO12/TOUCH12/ADC2_CH1/FSPICLK/FSPIIO6/SUBSPICLK_16") (pintype "passive"))
    )
    (net (code "35") (name "/GPIO13") (class "Default")
      (node (ref "J1") (pin "16") (pinfunction "16_16") (pintype "passive"))
      (node (ref "U1") (pin "17") (pinfunction "GPIO13/RTC_GPIO13/TOUCH13/ADC2_CH2/FSPIQ/FSPIIO7/SUBSPIQ_17") (pintype "passive"))
    )
    (net (code "36") (name "/GPIO14") (class "Default")
      (node (ref "J1") (pin "17") (pinfunction "17_17") (pintype "passive"))
      (node (ref "U1") (pin "18") (pinfunction "GPIO14/RTC_GPIO14/TOUCH14/ADC2_CH3/FSPIWP/FSPIDQS/SUBSPIWP_18") (pintype "passive"))
    )
    (net (code "37") (name "/GPIO15") (class "Default")
      (node (ref "J1") (pin "18") (pinfunction "18_18") (pintype "passive"))
      (node (ref "U1") (pin "19") (pinfunction "GPIO15/RTC_GPIO15/U0RTS/ADC2_CH4/XTAL_32K_P_19") (pintype "passive"))
    )
    (net (code "38") (name "/GPIO16") (class "Default")
      (node (ref "J1") (pin "19") (pinfunction "19_19") (pintype "passive"))
      (node (ref "U1") (pin "20") (pinfunction "GPIO16/RTC_GPIO16/U0CTS/ADC2_CH5/XTAL_32K_N_20") (pintype "passive"))
    )
    (net (code "39") (name "/GPIO17") (class "Default")
      (node (ref "J1") (pin "20") (pinfunction "20_20") (pintype "passive"))
      (node (ref "U1") (pin "21") (pinfunction "GPIO17/RTC_GPIO17/U1TXD/ADC2_CH6_21") (pintype "passive"))
    )
    (net (code "40") (name "/GPIO18") (class "Default")
      (node (ref "J1") (pin "21") (pinfunction "21_21") (pintype "passive"))
      (node (ref "U1") (pin "22") (pinfunction "GPIO18/RTC_GPIO18/U1RXD/ADC2_CH7/CLK_OUT3_22") (pintype "passive"))
    )
    (net (code "41") (name "/GPIO21") (class "Default")
      (node (ref "J2") (pin "19") (pinfunction "19_19") (pintype "passive"))
      (node (ref "U1") (pin "25") (pinfunction "GPIO21/RTC_GPIO21_25") (pintype "passive"))
    )
    (net (code "42") (name "/GPIO26") (class "Default")
      (node (ref "J2") (pin "18") (pinfunction "18_18") (pintype "passive"))
      (node (ref "U1") (pin "26") (pinfunction "GPIO26/SPICS1_26") (pintype "passive"))
    )
    (net (code "43") (name "/GPIO33") (class "Default")
      (node (ref "J2") (pin "17") (pinfunction "17_17") (pintype "passive"))
      (node (ref "U1") (pin "28") (pinfunction "GPIO33/SPIIO4/FSPIHD/SUBSPIHD_28") (pintype "passive"))
    )
    (net (code "44") (name "/GPIO34") (class "Default")
      (node (ref "J2") (pin "16") (pinfunction "16_16") (pintype "passive"))
      (node (ref "U1") (pin "29") (pinfunction "GPIO34/SPIIO5/FSPICS0/SUBSPICS0_29") (pintype "passive"))
    )
    (net (code "45") (name "/GPIO35") (class "Default")
      (node (ref "J2") (pin "15") (pinfunction "15_15") (pintype "passive"))
      (node (ref "U1") (pin "31") (pinfunction "GPIO35/SPIIO6/FSPID/SUBSPID_31") (pintype "passive"))
    )
    (net (code "46") (name "/GPIO36") (class "Default")
      (node (ref "J2") (pin "14") (pinfunction "14_14") (pintype "passive"))
      (node (ref "U1") (pin "32") (pinfunction "GPIO36/SPIIO7/FSPICLK/SUBSPICLK_32") (pintype "passive"))
    )
    (net (code "47") (name "/GPIO37") (class "Default")
      (node (ref "J2") (pin "13") (pinfunction "13_13") (pintype "passive"))
      (node (ref "U1") (pin "33") (pinfunction "GPIO37/SPIDQS/FSPIQ/SUBSPIQ_33") (pintype "passive"))
    )
    (net (code "48") (name "/GPIO38") (class "Default")
      (node (ref "J2") (pin "12") (pinfunction "12_12") (pintype "passive"))
      (node (ref "U1") (pin "34") (pinfunction "GPIO38/FSPIWP/SUBSPIWP_34") (pintype "passive"))
    )
    (net (code "49") (name "/GPIO39") (class "Default")
      (node (ref "J2") (pin "11") (pinfunction "11_11") (pintype "passive"))
      (node (ref "U1") (pin "35") (pinfunction "MTCK/GPIO39/CLK_OUT3/SUBSPICS1_35") (pintype "passive"))
    )
    (net (code "50") (name "/GPIO40") (class "Default")
      (node (ref "J2") (pin "10") (pinfunction "10_10") (pintype "passive"))
      (node (ref "U1") (pin "36") (pinfunction "MTDO/GPIO40/CLK_OUT2_36") (pintype "passive"))
    )
    (net (code "51") (name "/GPIO41") (class "Default")
      (node (ref "J2") (pin "9") (pinfunction "9_9") (pintype "passive"))
      (node (ref "U1") (pin "37") (pinfunction "MTDI/GPIO41/CLK_OUT1_37") (pintype "passive"))
    )
    (net (code "52") (name "/GPIO42") (class "Default")
      (node (ref "J2") (pin "8") (pinfunction "8_8") (pintype "passive"))
      (node (ref "U1") (pin "38") (pinfunction "MTMS/GPIO42_38") (pintype "passive"))
    )
    (net (code "53") (name "/GPIO45") (class "Default")
      (node (ref "J2") (pin "5") (pinfunction "5_5") (pintype "passive"))
      (node (ref "U1") (pin "41") (pinfunction "GPIO45_41") (pintype "passive"))
    )
    (net (code "54") (name "/GPIO46") (class "Default")
      (node (ref "J2") (pin "4") (pinfunction "4_4") (pintype "passive"))
      (node (ref "U1") (pin "44") (pinfunction "GPIO46_44") (pintype "passive"))
    )
    (net (code "55") (name "/GPIO47") (class "Default")
      (node (ref "J2") (pin "23") (pinfunction "23_23") (pintype "passive"))
      (node (ref "U1") (pin "27") (pinfunction "GPIO47/SPICLK_P_DIFF/SUBSPICLK_P_DIFF_27") (pintype "passive"))
    )
    (net (code "56") (name "/GPIO48") (class "Default")
      (node (ref "J2") (pin "22") (pinfunction "22_22") (pintype "passive"))
      (node (ref "U1") (pin "30") (pinfunction "GPIO48/SPICLK_N_DIFF/SUBSPICLK_N_DIFF_30") (pintype "passive"))
    )
    (net (code "57") (name "/RTS_FTDI") (class "Default")
      (node (ref "Q1") (pin "2") (pinfunction "E_2") (pintype "passive"))
      (node (ref "R26") (pin "2") (pinfunction "2_2") (pintype "passive"))
      (node (ref "U2") (pin "19") (pinfunction "~{RTS}_19") (pintype "passive"))
    )
    (net (code "58") (name "/RXD_FTDI") (class "Default")
      (node (ref "R20") (pin "2") (pinfunction "2_2") (pintype "passive"))
      (node (ref "U2") (pin "1") (pinfunction "RXD_1") (pintype "passive"))
    )
    (net (code "59") (name "/TXD_FTDI") (class "Default")
      (node (ref "R19") (pin "2") (pinfunction "2_2") (pintype "passive"))
      (node (ref "U2") (pin "17") (pinfunction "TXD_17") (pintype "passive"))
    )
    (net (code "60") (name "/U0RXD") (class "Default")
      (node (ref "J2") (pin "6") (pinfunction "6_6") (pintype "passive"))
      (node (ref "R19") (pin "1") (pinfunction "1_1") (pintype "passive"))
      (node (ref "U1") (pin "40") (pinfunction "U0RXD/GPIO44/CLK_OUT2_40") (pintype "passive"))
    )
    (net (code "61") (name "/U0TXD") (class "Default")
      (node (ref "J2") (pin "7") (pinfunction "7_7") (pintype "passive"))
      (node (ref "R20") (pin "1") (pinfunction "1_1") (pintype "passive"))
      (node (ref "U1") (pin "39") (pinfunction "U0TXD/GPIO43/CLK_OUT1_39") (pintype "passive"))
    )
    (net (code "62") (name "/VBUS _SENSE") (class "Default")
      (node (ref "R7") (pin "1") (pinfunction "1_1") (pintype "passive"))
      (node (ref "R9") (pin "2") (pinfunction "2_2") (pintype "passive"))
      (node (ref "U2") (pin "16") (pinfunction "CBUS3_16") (pintype "passive"))
    )
    (net (code "63") (name "GND") (class "Default")
      (node (ref "C1") (pin "1") (pinfunction "1_1") (pintype "passive"))
      (node (ref "C10") (pin "1") (pinfunction "1_1") (pintype "passive"))
      (node (ref "C12") (pin "1") (pinfunction "1_1") (pintype "passive"))
      (node (ref "C13") (pin "1") (pinfunction "1_1") (pintype "passive"))
      (node (ref "C14") (pin "1") (pinfunction "1_1") (pintype "passive"))
      (node (ref "C15") (pin "1") (pinfunction "1_1") (pintype "passive"))
      (node (ref "C16") (pin "1") (pinfunction "1_1") (pintype "passive"))
      (node (ref "C2") (pin "1") (pinfunction "1_1") (pintype "passive"))
      (node (ref "C3") (pin "1") (pinfunction "1_1") (pintype "passive"))
      (node (ref "C4") (pin "1") (pinfunction "1_1") (pintype "passive"))
      (node (ref "C5") (pin "1") (pinfunction "1_1") (pintype "passive"))
      (node (ref "C6") (pin "1") (pinfunction "1_1") (pintype "passive"))
      (node (ref "C7") (pin "1") (pinfunction "1_1") (pintype "passive"))
      (node (ref "C8") (pin "1") (pinfunction "1_1") (pintype "passive"))
      (node (ref "C9") (pin "1") (pinfunction "1_1") (pintype "passive"))
      (node (ref "D1") (pin "2") (pinfunction "2_2") (pintype "passive"))
      (node (ref "D2") (pin "2") (pinfunction "2_2") (pintype "passive"))
      (node (ref "D3") (pin "2") (pinfunction "2_2") (pintype "passive"))
      (node (ref "D4") (pin "2") (pinfunction "2_2") (pintype "passive"))
      (node (ref "D5") (pin "2") (pinfunction "2_2") (pintype "passive"))
      (node (ref "D6") (pin "2") (pinfunction "2_2") (pintype "passive"))
      (node (ref "D7") (pin "1") (pinfunction "1_1") (pintype "passive"))
      (node (ref "J1") (pin "1") (pinfunction "1_1") (pintype "passive"))
      (node (ref "J1") (pin "23") (pinfunction "23_23") (pintype "passive"))
      (node (ref "J2") (pin "2") (pinfunction "2_2") (pintype "passive"))
      (node (ref "J2") (pin "24") (pinfunction "24_24") (pintype "passive"))
      (node (ref "J3") (pin "A1_B12") (pinfunction "GND_A1B12_A1_B12") (pintype "passive"))
      (node (ref "J3") (pin "B1_A12") (pinfunction "GND_B1A12_B1_A12") (pintype "passive"))
      (node (ref "J3") (pin "S1") (pinfunction "SHIELD_1_S1") (pintype "passive"))
      (node (ref "J3") (pin "S2") (pinfunction "SHIELD_2_S2") (pintype "passive"))
      (node (ref "J3") (pin "S3") (pinfunction "SHIELD_3_S3") (pintype "passive"))
      (node (ref "J3") (pin "S4") (pinfunction "SHIELD_4_S4") (pintype "passive"))
      (node (ref "J4") (pin "A1_B12") (pinfunction "GND_A1B12_A1_B12") (pintype "passive"))
      (node (ref "J4") (pin "B1_A12") (pinfunction "GND_B1A12_B1_A12") (pintype "passive"))
      (node (ref "J4") (pin "S1") (pinfunction "SHIELD_1_S1") (pintype "passive"))
      (node (ref "J4") (pin "S2") (pinfunction "SHIELD_2_S2") (pintype "passive"))
      (node (ref "J4") (pin "S3") (pinfunction "SHIELD_3_S3") (pintype "passive"))
      (node (ref "J4") (pin "S4") (pinfunction "SHIELD_4_S4") (pintype "passive"))
      (node (ref "R10") (pin "1") (pinfunction "1_1") (pintype "passive"))
      (node (ref "R11") (pin "1") (pinfunction "1_1") (pintype "passive"))
      (node (ref "R12") (pin "1") (pinfunction "1_1") (pintype "passive"))
      (node (ref "R13") (pin "1") (pinfunction "1_1") (pintype "passive"))
      (node (ref "R8") (pin "2") (pinfunction "2_2") (pintype "passive"))
      (node (ref "R9") (pin "1") (pinfunction "1_1") (pintype "passive"))
      (node (ref "SW1") (pin "3") (pinfunction "3_3") (pintype "passive"))
      (node (ref "SW1") (pin "4") (pinfunction "4_4") (pintype "passive"))
      (node (ref "SW2") (pin "3") (pinfunction "3_3") (pintype "passive"))
      (node (ref "SW2") (pin "4") (pinfunction "4_4") (pintype "passive"))
      (node (ref "U1") (pin "1") (pinfunction "GND_01_1") (pintype "passive"))
      (node (ref "U1") (pin "2") (pinfunction "GND_02_2") (pintype "passive"))
      (node (ref "U1") (pin "42") (pinfunction "GND_42") (pintype "passive"))
      (node (ref "U1") (pin "43") (pinfunction "GND_43") (pintype "passive"))
      (node (ref "U1") (pin "46") (pinfunction "GND_46_46") (pintype "passive"))
      (node (ref "U1") (pin "47") (pinfunction "GND_47_47") (pintype "passive"))
      (node (ref "U1") (pin "48") (pinfunction "GND_48_48") (pintype "passive"))
      (node (ref "U1") (pin "49") (pinfunction "GND_49_49") (pintype "passive"))
      (node (ref "U1") (pin "50") (pinfunction "GND_50_50") (pintype "passive"))
      (node (ref "U1") (pin "51") (pinfunction "GND_51_51") (pintype "passive"))
      (node (ref "U1") (pin "52") (pinfunction "GND_52_52") (pintype "passive"))
      (node (ref "U1") (pin "53") (pinfunction "GND_53_53") (pintype "passive"))
      (node (ref "U1") (pin "54") (pinfunction "GND_54_54") (pintype "passive"))
      (node (ref "U1") (pin "55") (pinfunction "GND_55_55") (pintype "passive"))
      (node (ref "U1") (pin "56") (pinfunction "GND_56_56") (pintype "passive"))
      (node (ref "U1") (pin "57") (pinfunction "GND_57_57") (pintype "passive"))
      (node (ref "U1") (pin "58") (pinfunction "GND_58_58") (pintype "passive"))
      (node (ref "U1") (pin "59") (pinfunction "GND_59_59") (pintype "passive"))
      (node (ref "U1") (pin "60") (pinfunction "GND_60_60") (pintype "passive"))
      (node (ref "U1") (pin "61") (pinfunction "GND_61_61") (pintype "passive"))
      (node (ref "U1") (pin "62") (pinfunction "GND_62_62") (pintype "passive"))
      (node (ref "U1") (pin "63") (pinfunction "GND_63_63") (pintype "passive"))
      (node (ref "U1") (pin "64") (pinfunction "GND_64_64") (pintype "passive"))
      (node (ref "U1") (pin "65") (pinfunction "GND_65_65") (pintype "passive"))
      (node (ref "U1") (pin "66") (pinfunction "GND_66_66") (pintype "passive"))
      (node (ref "U1") (pin "67") (pinfunction "GND_67_67") (pintype "passive"))
      (node (ref "U1") (pin "68") (pinfunction "GND_68_68") (pintype "passive"))
      (node (ref "U1") (pin "69") (pinfunction "GND_69_69") (pintype "passive"))
      (node (ref "U1") (pin "70") (pinfunction "GND_70_70") (pintype "passive"))
      (node (ref "U1") (pin "71") (pinfunction "GND_71_71") (pintype "passive"))
      (node (ref "U1") (pin "72") (pinfunction "GND_72_72") (pintype "passive"))
      (node (ref "U1") (pin "73") (pinfunction "GND_73_73") (pintype "passive"))
      (node (ref "U2") (pin "13") (pinfunction "GND_13") (pintype "passive"))
      (node (ref "U2") (pin "21") (pinfunction "GND_21") (pintype "passive"))
      (node (ref "U2") (pin "3") (pinfunction "GND_3") (pintype "passive"))
      (node (ref "U3") (pin "1") (pinfunction "PGND_1") (pintype "passive"))
      (node (ref "U3") (pin "4") (pinfunction "AGND_4") (pintype "passive"))
      (node (ref "U3") (pin "5") (pinfunction "FB_5") (pintype "passive"))
    )
    (net (code "64") (name "Net-(D7-Pad2)") (class "Default")
      (node (ref "D7") (pin "2") (pinfunction "2_2") (pintype "passive"))
      (node (ref "R15") (pin "1") (pinfunction "1_1") (pintype "passive"))
    )
    (net (code "65") (name "Net-(D8-Pad2)") (class "Default")
      (node (ref "D8") (pin "2") (pinfunction "2_2") (pintype "passive"))
      (node (ref "R16") (pin "1") (pinfunction "1_1") (pintype "passive"))
    )
    (net (code "66") (name "Net-(J3-CC1)") (class "Default")
      (node (ref "J3") (pin "A5") (pinfunction "CC1_A5") (pintype "passive"))
      (node (ref "R11") (pin "2") (pinfunction "2_2") (pintype "passive"))
    )
    (net (code "67") (name "Net-(J3-CC2)") (class "Default")
      (node (ref "J3") (pin "B5") (pinfunction "CC2_B5") (pintype "passive"))
      (node (ref "R10") (pin "2") (pinfunction "2_2") (pintype "passive"))
    )
    (net (code "68") (name "Net-(J4-CC1)") (class "Default")
      (node (ref "J4") (pin "A5") (pinfunction "CC1_A5") (pintype "passive"))
      (node (ref "R13") (pin "2") (pinfunction "2_2") (pintype "passive"))
    )
    (net (code "69") (name "Net-(J4-CC2)") (class "Default")
      (node (ref "J4") (pin "B5") (pinfunction "CC2_B5") (pintype "passive"))
      (node (ref "R12") (pin "2") (pinfunction "2_2") (pintype "passive"))
    )
    (net (code "70") (name "Net-(Q1-B)") (class "Default")
      (node (ref "Q1") (pin "1") (pinfunction "B_1") (pintype "passive"))
      (node (ref "R21") (pin "1") (pinfunction "1_1") (pintype "passive"))
    )
    (net (code "71") (name "Net-(Q2-B)") (class "Default")
      (node (ref "Q2") (pin "1") (pinfunction "B_1") (pintype "passive"))
      (node (ref "R26") (pin "1") (pinfunction "1_1") (pintype "passive"))
    )
    (net (code "72") (name "Net-(U2-CBUS0)") (class "Default")
      (node (ref "R8") (pin "1") (pinfunction "1_1") (pintype "passive"))
      (node (ref "U2") (pin "15") (pinfunction "CBUS0_15") (pintype "passive"))
    )
    (net (code "73") (name "Net-(U2-~{RESET})") (class "Default")
      (node (ref "C9") (pin "2") (pinfunction "2_2") (pintype "passive"))
      (node (ref "R5") (pin "2") (pinfunction "2_2") (pintype "passive"))
      (node (ref "U2") (pin "11") (pinfunction "~{RESET}_11") (pintype "passive"))
    )
    (net (code "74") (name "Net-(U3-PG)") (class "Default")
      (node (ref "R23") (pin "1") (pinfunction "1_1") (pintype "passive"))
      (node (ref "U3") (pin "8") (pinfunction "PG_8") (pintype "passive"))
    )
    (net (code "75") (name "Net-(U3-SW)") (class "Default")
      (node (ref "L1") (pin "1") (pinfunction "1_1") (pintype "passive"))
      (node (ref "U3") (pin "7") (pinfunction "SW_7") (pintype "passive"))
    )
    (net (code "76") (name "unconnected-(J1-Pad24)") (class "Default")
      (node (ref "J1") (pin "24") (pinfunction "24_24") (pintype "passive+no_connect"))
    )
    (net (code "77") (name "unconnected-(J3-SUB1-PadA8)") (class "Default")
      (node (ref "J3") (pin "A8") (pinfunction "SUB1_A8") (pintype "passive+no_connect"))
    )
    (net (code "78") (name "unconnected-(J3-SUB2-PadB8)") (class "Default")
      (node (ref "J3") (pin "B8") (pinfunction "SUB2_B8") (pintype "passive+no_connect"))
    )
    (net (code "79") (name "unconnected-(J4-SUB1-PadA8)") (class "Default")
      (node (ref "J4") (pin "A8") (pinfunction "SUB1_A8") (pintype "passive+no_connect"))
    )
    (net (code "80") (name "unconnected-(J4-SUB2-PadB8)") (class "Default")
      (node (ref "J4") (pin "B8") (pinfunction "SUB2_B8") (pintype "passive+no_connect"))
    )
    (net (code "81") (name "unconnected-(U2-CBUS1-Pad14)") (class "Default")
      (node (ref "U2") (pin "14") (pinfunction "CBUS1_14") (pintype "passive+no_connect"))
    )
    (net (code "82") (name "unconnected-(U2-CBUS2-Pad7)") (class "Default")
      (node (ref "U2") (pin "7") (pinfunction "CBUS2_7") (pintype "passive+no_connect"))
    )
    (net (code "83") (name "unconnected-(U2-~{CTS}-Pad6)") (class "Default")
      (node (ref "U2") (pin "6") (pinfunction "~{CTS}_6") (pintype "passive+no_connect"))
    )
    (net (code "84") (name "unconnected-(U2-~{DCD}-Pad5)") (class "Default")
      (node (ref "U2") (pin "5") (pinfunction "~{DCD}_5") (pintype "passive+no_connect"))
    )
    (net (code "85") (name "unconnected-(U2-~{DSR}-Pad4)") (class "Default")
      (node (ref "U2") (pin "4") (pinfunction "~{DSR}_4") (pintype "passive+no_connect"))
    )
    (net (code "86") (name "unconnected-(U2-~{RI}-Pad2)") (class "Default")
      (node (ref "U2") (pin "2") (pinfunction "~{RI}_2") (pintype "passive+no_connect"))
    )
  )
)
